# MOD-COIL-LN2-21.net
KiCad netlist of a schematic drawn in Altium Designer
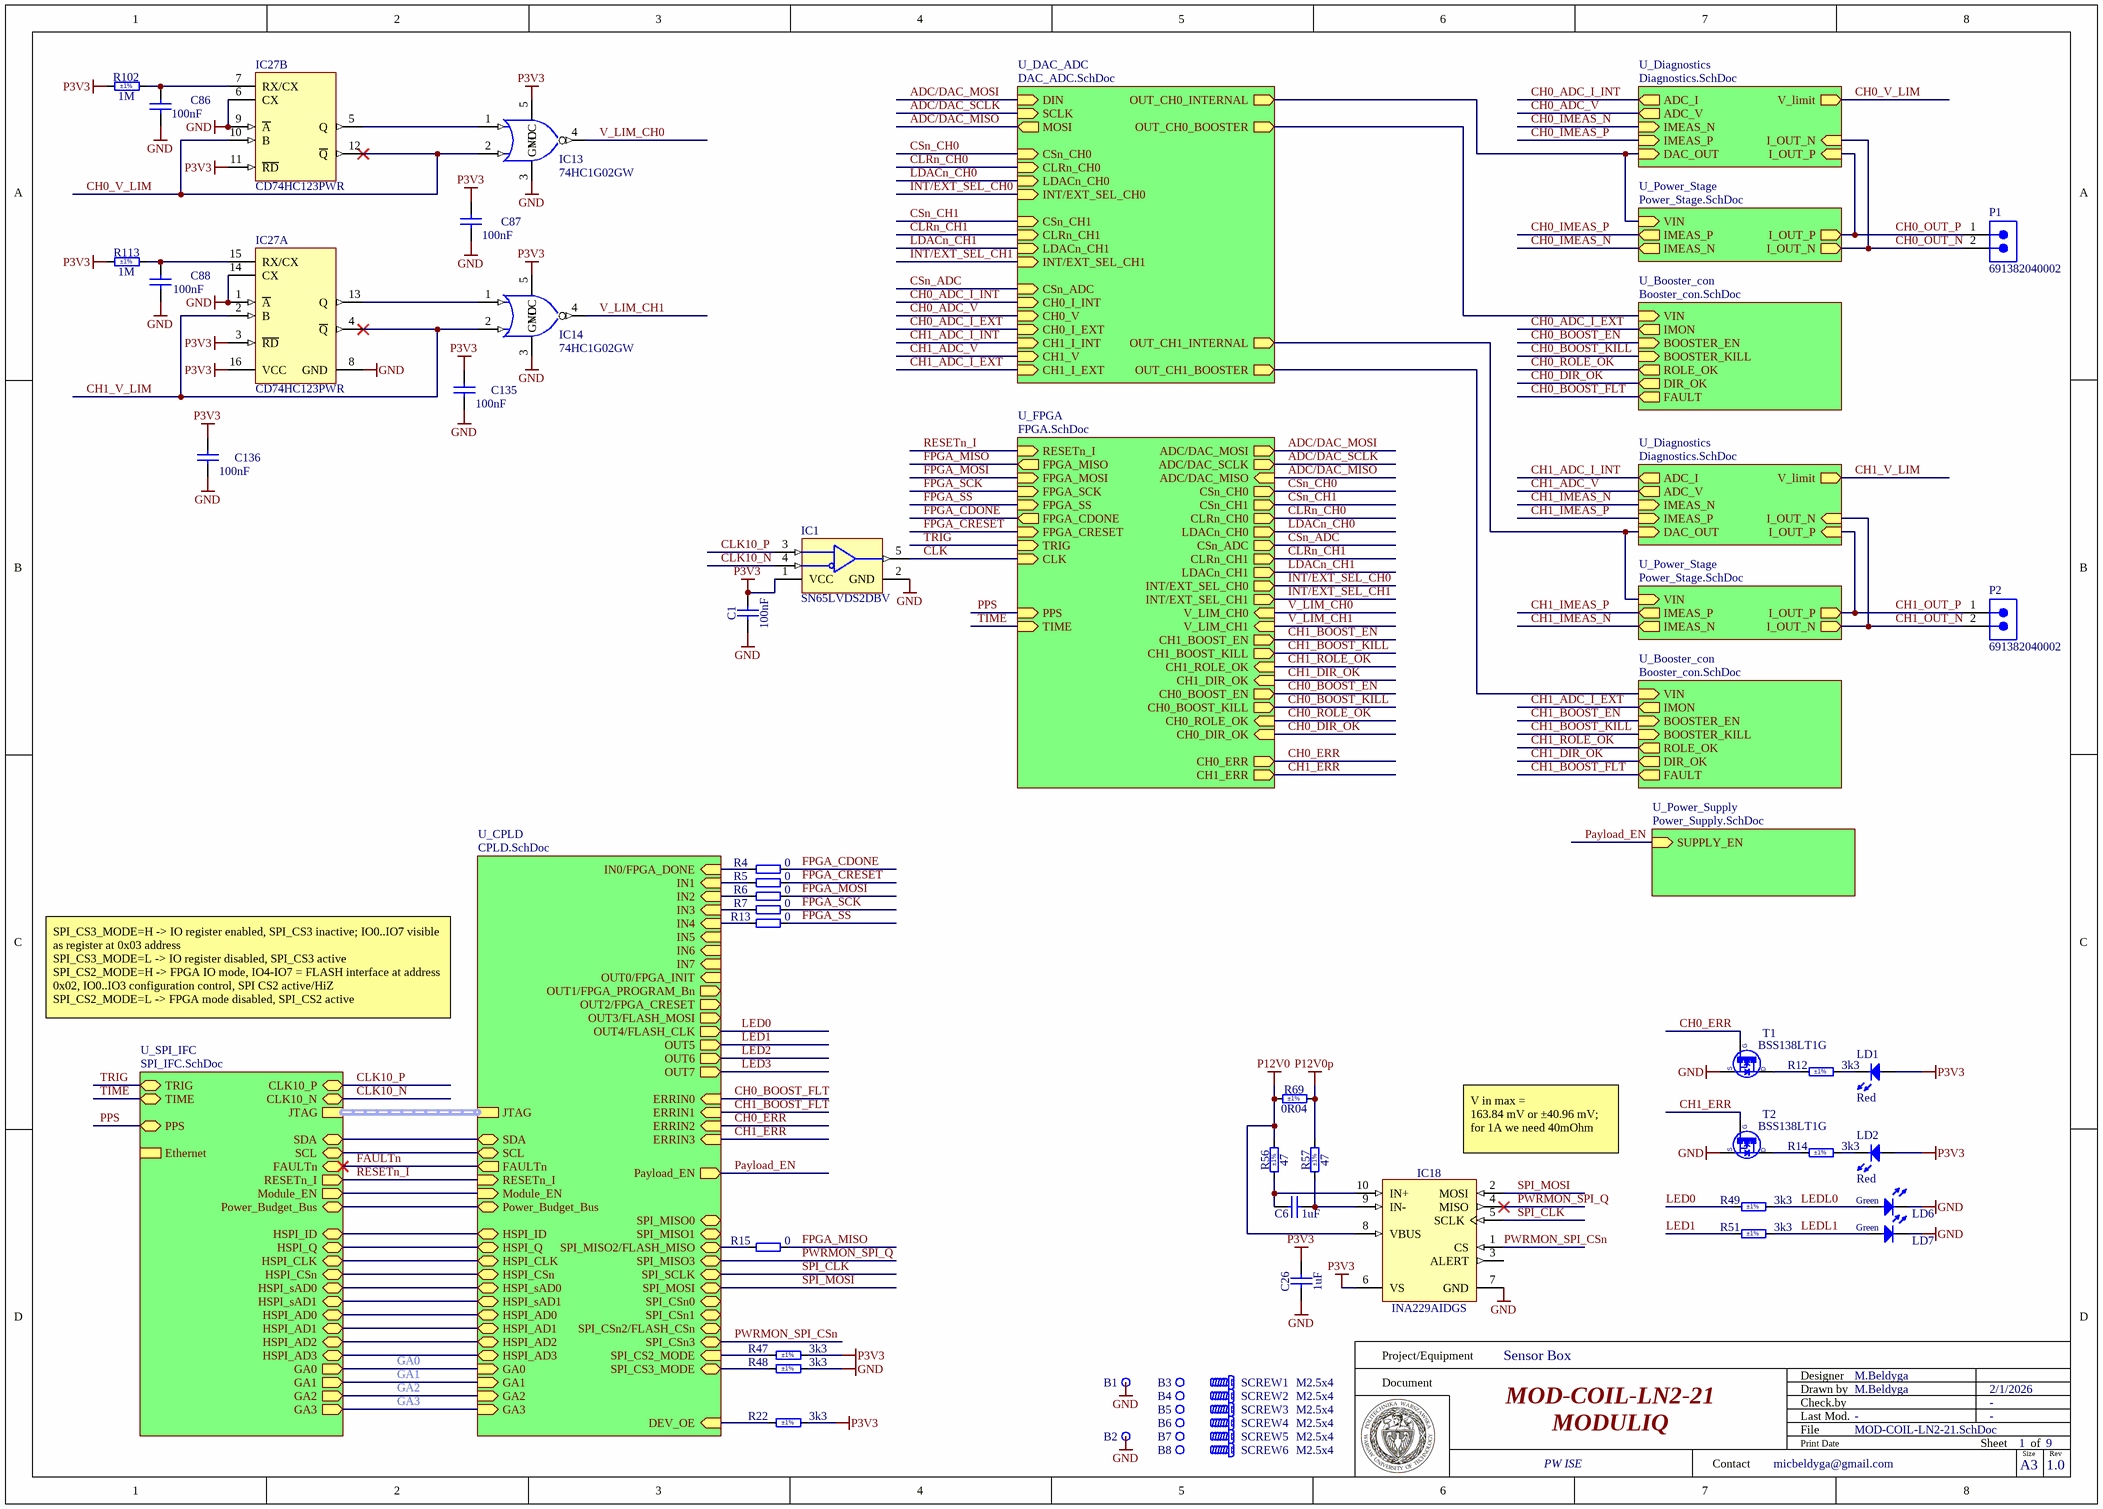
[diagram p0: MOD-COIL-LN2-21.SchDoc]

(export (version "E")
  (design (tool "Eeschema 10.0.6"))
  (components
    (comp (ref "B1")
      (value "Plated Hole")
      (footprint "MTG270_500")
      (description "Single Terminal Socket")
      (fields (field (name "PART NUMBER") "PLATED_HOLE2.7_PAD5.0") (field (name "AUTHOR") "CERN DEM JMW"))
      (libsource (lib "Eletro-mechanical") (part "Single Terminal Socket"))
    )
    (comp (ref "B2")
      (value "Plated Hole")
      (footprint "MTG270_500")
      (description "Single Terminal Socket")
      (fields (field (name "PART NUMBER") "PLATED_HOLE2.7_PAD5.0") (field (name "AUTHOR") "CERN DEM JMW"))
      (libsource (lib "Eletro-mechanical") (part "Single Terminal Socket"))
    )
    (comp (ref "B3")
      (value "Plated Hole")
      (footprint "MTG270_500")
      (description "Single Terminal Socket")
      (fields (field (name "PART NUMBER") "PLATED_HOLE2.7_PAD5.0") (field (name "AUTHOR") "CERN DEM JMW"))
      (libsource (lib "Eletro-mechanical") (part "Single Terminal Socket"))
    )
    (comp (ref "B4")
      (value "Plated Hole")
      (footprint "MTG270_500")
      (description "Single Terminal Socket")
      (fields (field (name "PART NUMBER") "PLATED_HOLE2.7_PAD5.0") (field (name "AUTHOR") "CERN DEM JMW"))
      (libsource (lib "Eletro-mechanical") (part "Single Terminal Socket"))
    )
    (comp (ref "B5")
      (value "Plated Hole")
      (footprint "MTG270_500")
      (description "Single Terminal Socket")
      (fields (field (name "PART NUMBER") "PLATED_HOLE2.7_PAD5.0") (field (name "AUTHOR") "CERN DEM JMW"))
      (libsource (lib "Eletro-mechanical") (part "Single Terminal Socket"))
    )
    (comp (ref "B6")
      (value "Plated Hole")
      (footprint "MTG270_500")
      (description "Single Terminal Socket")
      (fields (field (name "PART NUMBER") "PLATED_HOLE2.7_PAD5.0") (field (name "AUTHOR") "CERN DEM JMW"))
      (libsource (lib "Eletro-mechanical") (part "Single Terminal Socket"))
    )
    (comp (ref "B7")
      (value "Plated Hole")
      (footprint "MTG270_500")
      (description "Single Terminal Socket")
      (fields (field (name "PART NUMBER") "PLATED_HOLE2.7_PAD5.0") (field (name "AUTHOR") "CERN DEM JMW"))
      (libsource (lib "Eletro-mechanical") (part "Single Terminal Socket"))
    )
    (comp (ref "B8")
      (value "Plated Hole")
      (footprint "MTG270_500")
      (description "Single Terminal Socket")
      (fields (field (name "PART NUMBER") "PLATED_HOLE2.7_PAD5.0") (field (name "AUTHOR") "CERN DEM JMW"))
      (libsource (lib "Eletro-mechanical") (part "Single Terminal Socket"))
    )
    (comp (ref "C1")
      (value "100nF")
      (footprint "CAPC1005X55N")
      (description "Non-polarised capacitor")
      (fields
        (field (name "PART NUMBER") "CC0402_100NF_16V_10%_X7R")
        (field (name "VOLTAGE") "16V")
        (field (name "AUTHOR") "CERN DEM JLC")
      )
      (libsource (lib "Capacitors") (part "Capacitor - non polarized"))
    )
    (comp (ref "C6")
      (value "1uF")
      (footprint "CAPC1005X55N")
      (description "Non-polarised capacitor")
      (fields
        (field (name "PART NUMBER") "CC0402_1UF_16V_10%_X5R")
        (field (name "VOLTAGE") "16V")
        (field (name "AUTHOR") "CERN DEM JLC")
      )
      (libsource (lib "Capacitors") (part "Capacitor - non polarized"))
    )
    (comp (ref "C26")
      (value "1uF")
      (footprint "CAPC1005X55N")
      (description "Non-polarised capacitor")
      (fields
        (field (name "PART NUMBER") "CC0402_1UF_16V_10%_X5R")
        (field (name "VOLTAGE") "16V")
        (field (name "AUTHOR") "CERN DEM JLC")
      )
      (libsource (lib "Capacitors") (part "Capacitor - non polarized"))
    )
    (comp (ref "C86")
      (value "100nF")
      (footprint "CAPC1005X55N")
      (description "Non-polarised capacitor")
      (fields
        (field (name "PART NUMBER") "CC0402_100NF_16V_10%_X5R")
        (field (name "VOLTAGE") "16V")
        (field (name "AUTHOR") "CERN DEM JLC")
      )
      (libsource (lib "Capacitors") (part "Capacitor - non polarized"))
    )
    (comp (ref "C87")
      (value "100nF")
      (footprint "CAPC1005X55N")
      (description "Non-polarised capacitor")
      (fields
        (field (name "PART NUMBER") "CC0402_100NF_16V_10%_X5R")
        (field (name "VOLTAGE") "16V")
        (field (name "AUTHOR") "CERN DEM JLC")
      )
      (libsource (lib "Capacitors") (part "Capacitor - non polarized"))
    )
    (comp (ref "C88")
      (value "100nF")
      (footprint "CAPC1005X55N")
      (description "Non-polarised capacitor")
      (fields
        (field (name "PART NUMBER") "CC0402_100NF_16V_10%_X5R")
        (field (name "VOLTAGE") "16V")
        (field (name "AUTHOR") "CERN DEM JLC")
      )
      (libsource (lib "Capacitors") (part "Capacitor - non polarized"))
    )
    (comp (ref "C135")
      (value "100nF")
      (footprint "CAPC1005X55N")
      (description "Non-polarised capacitor")
      (fields
        (field (name "PART NUMBER") "CC0402_100NF_16V_10%_X5R")
        (field (name "VOLTAGE") "16V")
        (field (name "AUTHOR") "CERN DEM JLC")
      )
      (libsource (lib "Capacitors") (part "Capacitor - non polarized"))
    )
    (comp (ref "C136")
      (value "100nF")
      (footprint "CAPC1005X55N")
      (description "Non-polarised capacitor")
      (fields
        (field (name "PART NUMBER") "CC0402_100NF_16V_10%_X5R")
        (field (name "VOLTAGE") "16V")
        (field (name "AUTHOR") "CERN DEM JLC")
      )
      (libsource (lib "Capacitors") (part "Capacitor - non polarized"))
    )
    (comp (ref "IC1")
      (value "SN65LVDS2DBV")
      (footprint "SOT95P280X145-5N")
      (description "High-Speed Differential Line Receiver")
      (fields
        (field (name "PART NUMBER") "SN65LVDS2DBVR")
        (field (name "MANUFACTURER") "TEXAS INSTRUMENTS")
        (field (name "AUTHOR") "CERN DEM JLC")
      )
      (libsource (lib "ICs And Semiconductors") (part "SN65LVDS2DBV"))
    )
    (comp (ref "IC13")
      (value "74HC1G02GW")
      (footprint "SOT65P212X110-5N")
      (description "Single 2-Input NOR Gate")
      (fields (field (name "MANUFACTURER") "NEXPERIA") (field (name "AUTHOR") "CERN DEM MR"))
      (libsource (lib "ICs And Semiconductors") (part "741G02"))
    )
    (comp (ref "IC14")
      (value "74HC1G02GW")
      (footprint "SOT65P212X110-5N")
      (description "Single 2-Input NOR Gate")
      (fields (field (name "MANUFACTURER") "NEXPERIA") (field (name "AUTHOR") "CERN DEM MR"))
      (libsource (lib "ICs And Semiconductors") (part "741G02"))
    )
    (comp (ref "IC18")
      (value "INA229AIDGS")
      (footprint "SOP50P490X110-10N")
      (description "20-Bit, Ultra-Precise Power/Energy/Charge Monitor With SPI Interface")
      (fields (field (name "MANUFACTURER") "TEXAS INSTRUMENTS") (field (name "AUTHOR") "CERN DEM HF"))
      (libsource (lib "ICs And Semiconductors") (part "INA229"))
    )
    (comp (ref "IC27")
      (value "CD74HC123PWR")
      (footprint "SOP65P640X110-16N")
      (description "Monostable Multivibrator Dual 16-Pin TSSOP T/R - Tape and Reel (Alt: CD74HC123PW")
      (fields (field (name "MANUFACTURER") "Texas Instruments"))
      (libsource (lib "mb") (part "CD74HC123PWR"))
    )
    (comp (ref "LD1")
      (value "Red")
      (footprint "LED_AVAGO_HSMC-C120")
      (description "LED Red 1C 2A")
      (fields
        (field (name "PART NUMBER") "LED_AVAGO_HSMC-C120")
        (field (name "MANUFACTURER") "AVAGO TECHNOLOGIES")
        (field (name "AUTHOR") "CERN DEM JMW")
      )
      (libsource (lib "ICs And Semiconductors") (part "LED Red 1C 2A"))
    )
    (comp (ref "LD2")
      (value "Red")
      (footprint "LED_AVAGO_HSMC-C120")
      (description "LED Red 1C 2A")
      (fields
        (field (name "PART NUMBER") "LED_AVAGO_HSMC-C120")
        (field (name "MANUFACTURER") "AVAGO TECHNOLOGIES")
        (field (name "AUTHOR") "CERN DEM JMW")
      )
      (libsource (lib "ICs And Semiconductors") (part "LED Red 1C 2A"))
    )
    (comp (ref "LD6")
      (value "Green")
      (footprint "LED_AVAGO_HSME-C120")
      (description "LED Green 1C 2A")
      (fields
        (field (name "PART NUMBER") "LED_AVAGO_HSME-C120")
        (field (name "MANUFACTURER") "AVAGO TECHNOLOGIES")
        (field (name "AUTHOR") "CERN DEM JMW")
      )
      (libsource (lib "ICs And Semiconductors") (part "LED Green 1C 2A"))
    )
    (comp (ref "LD7")
      (value "Green")
      (footprint "LED_AVAGO_HSME-C120")
      (description "LED Green 1C 2A")
      (fields
        (field (name "PART NUMBER") "LED_AVAGO_HSME-C120")
        (field (name "MANUFACTURER") "AVAGO TECHNOLOGIES")
        (field (name "AUTHOR") "CERN DEM JMW")
      )
      (libsource (lib "ICs And Semiconductors") (part "LED Green 1C 2A"))
    )
    (comp (ref "P1")
      (value "691382040002")
      (footprint "691382040002")
      (description "WR-TBL Series 382 Horizontal PCB Header with Flanges, THT, pitch 2.5mm, 2p")
      (fields (field (name "MANUFACTURER") "Wurth Elektronik"))
      (libsource (lib "WE - Electromechanical Components") (part "TBL - 1R - 02P - Male"))
    )
    (comp (ref "P2")
      (value "691382040002")
      (footprint "691382040002")
      (description "WR-TBL Series 382 Horizontal PCB Header with Flanges, THT, pitch 2.5mm, 2p")
      (fields (field (name "MANUFACTURER") "Wurth Elektronik"))
      (libsource (lib "WE - Electromechanical Components") (part "TBL - 1R - 02P - Male"))
    )
    (comp (ref "R4")
      (value "0")
      (footprint "RESC1005X40N")
      (description "Resistor")
      (fields
        (field (name "PART NUMBER") "R0402_0R_JUMPER")
        (field (name "MANUFACTURER") "GENERIC")
        (field (name "AUTHOR") "CERN DEM JLC")
      )
      (libsource (lib "Resistors") (part "Resistor"))
    )
    (comp (ref "R5")
      (value "0")
      (footprint "RESC1005X40N")
      (description "Resistor")
      (fields
        (field (name "PART NUMBER") "R0402_0R_JUMPER")
        (field (name "MANUFACTURER") "GENERIC")
        (field (name "AUTHOR") "CERN DEM JLC")
      )
      (libsource (lib "Resistors") (part "Resistor"))
    )
    (comp (ref "R6")
      (value "0")
      (footprint "RESC1005X40N")
      (description "Resistor")
      (fields
        (field (name "PART NUMBER") "R0402_0R_JUMPER")
        (field (name "MANUFACTURER") "GENERIC")
        (field (name "AUTHOR") "CERN DEM JLC")
      )
      (libsource (lib "Resistors") (part "Resistor"))
    )
    (comp (ref "R7")
      (value "0")
      (footprint "RESC1005X40N")
      (description "Resistor")
      (fields
        (field (name "PART NUMBER") "R0402_0R_JUMPER")
        (field (name "MANUFACTURER") "GENERIC")
        (field (name "AUTHOR") "CERN DEM JLC")
      )
      (libsource (lib "Resistors") (part "Resistor"))
    )
    (comp (ref "R12")
      (value "3k3")
      (footprint "RESC1005X40N")
      (description "Resistor - 1%")
      (fields
        (field (name "TOLERANCE") "±1%")
        (field (name "PART NUMBER") "R0402_3K3_1%_0.0625W_100PPM")
        (field (name "POWER") "0.0625W")
        (field (name "AUTHOR") "CERN DEM JLC")
      )
      (libsource (lib "Resistors") (part "Resistor - 1%"))
    )
    (comp (ref "R13")
      (value "0")
      (footprint "RESC1005X40N")
      (description "Resistor")
      (fields
        (field (name "PART NUMBER") "R0402_0R_JUMPER")
        (field (name "MANUFACTURER") "GENERIC")
        (field (name "AUTHOR") "CERN DEM JLC")
      )
      (libsource (lib "Resistors") (part "Resistor"))
    )
    (comp (ref "R14")
      (value "3k3")
      (footprint "RESC1005X40N")
      (description "Resistor - 1%")
      (fields
        (field (name "TOLERANCE") "±1%")
        (field (name "PART NUMBER") "R0402_3K3_1%_0.0625W_100PPM")
        (field (name "POWER") "0.0625W")
        (field (name "AUTHOR") "CERN DEM JLC")
      )
      (libsource (lib "Resistors") (part "Resistor - 1%"))
    )
    (comp (ref "R15")
      (value "0")
      (footprint "RESC1005X40N")
      (description "Resistor")
      (fields
        (field (name "PART NUMBER") "R0402_0R_JUMPER")
        (field (name "MANUFACTURER") "GENERIC")
        (field (name "AUTHOR") "CERN DEM JLC")
      )
      (libsource (lib "Resistors") (part "Resistor"))
    )
    (comp (ref "R22")
      (value "3k3")
      (footprint "RESC1005X40N")
      (description "Resistor - 1%")
      (fields
        (field (name "TOLERANCE") "±1%")
        (field (name "PART NUMBER") "R0402_3K3_1%_0.0625W_100PPM")
        (field (name "POWER") "0.0625W")
        (field (name "AUTHOR") "CERN DEM JLC")
      )
      (libsource (lib "Resistors") (part "Resistor - 1%"))
    )
    (comp (ref "R47")
      (value "3k3")
      (footprint "RESC1005X40N")
      (description "Resistor - 1%")
      (fields
        (field (name "TOLERANCE") "±1%")
        (field (name "PART NUMBER") "R0402_3K3_1%_0.0625W_100PPM")
        (field (name "POWER") "0.0625W")
        (field (name "AUTHOR") "CERN DEM JLC")
      )
      (libsource (lib "Resistors") (part "Resistor - 1%"))
    )
    (comp (ref "R48")
      (value "3k3")
      (footprint "RESC1005X40N")
      (description "Resistor - 1%")
      (fields
        (field (name "TOLERANCE") "±1%")
        (field (name "PART NUMBER") "R0402_3K3_1%_0.0625W_100PPM")
        (field (name "POWER") "0.0625W")
        (field (name "AUTHOR") "CERN DEM JLC")
      )
      (libsource (lib "Resistors") (part "Resistor - 1%"))
    )
    (comp (ref "R49")
      (value "3k3")
      (footprint "RESC1005X40N")
      (description "Resistor - 1%")
      (fields
        (field (name "TOLERANCE") "±1%")
        (field (name "PART NUMBER") "R0402_3K3_1%_0.0625W_100PPM")
        (field (name "POWER") "0.0625W")
        (field (name "AUTHOR") "CERN DEM JLC")
      )
      (libsource (lib "Resistors") (part "Resistor - 1%"))
    )
    (comp (ref "R51")
      (value "3k3")
      (footprint "RESC1005X40N")
      (description "Resistor - 1%")
      (fields
        (field (name "TOLERANCE") "±1%")
        (field (name "PART NUMBER") "R0402_3K3_1%_0.0625W_100PPM")
        (field (name "POWER") "0.0625W")
        (field (name "AUTHOR") "CERN DEM JLC")
      )
      (libsource (lib "Resistors") (part "Resistor - 1%"))
    )
    (comp (ref "R56")
      (value "47")
      (footprint "RESC1608X55N")
      (description "Resistor - 1%")
      (fields
        (field (name "TOLERANCE") "±1%")
        (field (name "PART NUMBER") "R0603_47R_1%_0.1W_100PPM")
        (field (name "POWER") "0.1W")
        (field (name "AUTHOR") "CERN DEM JLC")
      )
      (libsource (lib "Resistors") (part "Resistor - 1%"))
    )
    (comp (ref "R57")
      (value "47")
      (footprint "RESC1608X55N")
      (description "Resistor - 1%")
      (fields
        (field (name "TOLERANCE") "±1%")
        (field (name "PART NUMBER") "R0603_47R_1%_0.1W_100PPM")
        (field (name "POWER") "0.1W")
        (field (name "AUTHOR") "CERN DEM JLC")
      )
      (libsource (lib "Resistors") (part "Resistor - 1%"))
    )
    (comp (ref "R69")
      (value "0R04")
      (footprint "RESC3216X89N")
      (description "Resistor - 1%")
      (fields
        (field (name "TOLERANCE") "±1%")
        (field (name "PART NUMBER") "R1206_0R04_1%_0.25W_75PPM_VISHAY_WSL")
        (field (name "POWER") "0.25W")
        (field (name "AUTHOR") "CERN DEM JMW")
      )
      (libsource (lib "Resistors") (part "Resistor - 1%"))
    )
    (comp (ref "R102")
      (value "1M")
      (footprint "RESC1005X40N")
      (description "Resistor - 1%")
      (fields
        (field (name "TOLERANCE") "±1%")
        (field (name "PART NUMBER") "R0402_1M_1%_0.0625W_100PPM")
        (field (name "POWER") "0.0625W")
        (field (name "AUTHOR") "CERN DEM JLC")
      )
      (libsource (lib "Resistors") (part "Resistor - 1%"))
    )
    (comp (ref "R113")
      (value "1M")
      (footprint "RESC1005X40N")
      (description "Resistor - 1%")
      (fields
        (field (name "TOLERANCE") "±1%")
        (field (name "PART NUMBER") "R0402_1M_1%_0.0625W_100PPM")
        (field (name "POWER") "0.0625W")
        (field (name "AUTHOR") "CERN DEM JLC")
      )
      (libsource (lib "Resistors") (part "Resistor - 1%"))
    )
    (comp (ref "SCREW1")
      (value "M2.5x4")
      (footprint "BOSSARD_BN5687-3061587_v")
      (description "Screw")
      (fields
        (field (name "PART NUMBER") "BOSSARD_BN5687-3061587_v")
        (field (name "MANUFACTURER") "BOSSARD")
        (field (name "AUTHOR") "CERN DEM JLC")
      )
      (libsource (lib "Eletro-mechanical") (part "Screw"))
    )
    (comp (ref "SCREW2")
      (value "M2.5x4")
      (footprint "BOSSARD_BN5687-3061587_v")
      (description "Screw")
      (fields
        (field (name "PART NUMBER") "BOSSARD_BN5687-3061587_v")
        (field (name "MANUFACTURER") "BOSSARD")
        (field (name "AUTHOR") "CERN DEM JLC")
      )
      (libsource (lib "Eletro-mechanical") (part "Screw"))
    )
    (comp (ref "SCREW3")
      (value "M2.5x4")
      (footprint "BOSSARD_BN5687-3061587_v")
      (description "Screw")
      (fields
        (field (name "PART NUMBER") "BOSSARD_BN5687-3061587_v")
        (field (name "MANUFACTURER") "BOSSARD")
        (field (name "AUTHOR") "CERN DEM JLC")
      )
      (libsource (lib "Eletro-mechanical") (part "Screw"))
    )
    (comp (ref "SCREW4")
      (value "M2.5x4")
      (footprint "BOSSARD_BN5687-3061587_v")
      (description "Screw")
      (fields
        (field (name "PART NUMBER") "BOSSARD_BN5687-3061587_v")
        (field (name "MANUFACTURER") "BOSSARD")
        (field (name "AUTHOR") "CERN DEM JLC")
      )
      (libsource (lib "Eletro-mechanical") (part "Screw"))
    )
    (comp (ref "SCREW5")
      (value "M2.5x4")
      (footprint "BOSSARD_BN5687-3061587_v")
      (description "Screw")
      (fields
        (field (name "PART NUMBER") "BOSSARD_BN5687-3061587_v")
        (field (name "MANUFACTURER") "BOSSARD")
        (field (name "AUTHOR") "CERN DEM JLC")
      )
      (libsource (lib "Eletro-mechanical") (part "Screw"))
    )
    (comp (ref "SCREW6")
      (value "M2.5x4")
      (footprint "BOSSARD_BN5687-3061587_v")
      (description "Screw")
      (fields
        (field (name "PART NUMBER") "BOSSARD_BN5687-3061587_v")
        (field (name "MANUFACTURER") "BOSSARD")
        (field (name "AUTHOR") "CERN DEM JLC")
      )
      (libsource (lib "Eletro-mechanical") (part "Screw"))
    )
    (comp (ref "T1")
      (value "BSS138LT1G")
      (footprint "SOT95P240X110-3N")
      (description "N-CHANNEL MOSFET WITH DIODE")
      (fields (field (name "AUTHOR") "CERN DEM JLC"))
      (libsource (lib "ICs And Semiconductors") (part "N-MOSFET-D 1G 2S 3D"))
    )
    (comp (ref "T2")
      (value "BSS138LT1G")
      (footprint "SOT95P240X110-3N")
      (description "N-CHANNEL MOSFET WITH DIODE")
      (fields (field (name "AUTHOR") "CERN DEM JLC"))
      (libsource (lib "ICs And Semiconductors") (part "N-MOSFET-D 1G 2S 3D"))
    )
  )
  (nets
    (net (code "11") (name "/CH0_ERR") (class "Default")
      (node (ref "T1") (pin "1") (pinfunction "G_1") (pintype "passive"))
    )
    (net (code "14") (name "/CH0_OUT_N") (class "Default")
      (node (ref "P1") (pin "2") (pinfunction "2_2") (pintype "passive"))
    )
    (net (code "15") (name "/CH0_OUT_P") (class "Default")
      (node (ref "P1") (pin "1") (pinfunction "1_1") (pintype "passive"))
    )
    (net (code "17") (name "/CH0_V_LIM") (class "Default")
      (node (ref "IC13") (pin "2") (pinfunction "A_2") (pintype "input"))
      (node (ref "IC27") (pin "10") (pinfunction "B_10") (pintype "input"))
      (node (ref "IC27") (pin "12") (pinfunction "~{Q}_12") (pintype "output"))
    )
    (net (code "25") (name "/CH1_ERR") (class "Default")
      (node (ref "T2") (pin "1") (pinfunction "G_1") (pintype "passive"))
    )
    (net (code "28") (name "/CH1_OUT_N") (class "Default")
      (node (ref "P2") (pin "2") (pinfunction "2_2") (pintype "passive"))
    )
    (net (code "29") (name "/CH1_OUT_P") (class "Default")
      (node (ref "P2") (pin "1") (pinfunction "1_1") (pintype "passive"))
    )
    (net (code "31") (name "/CH1_V_LIM") (class "Default")
      (node (ref "IC14") (pin "2") (pinfunction "A_2") (pintype "input"))
      (node (ref "IC27") (pin "2") (pinfunction "B_2") (pintype "input"))
      (node (ref "IC27") (pin "4") (pinfunction "~{Q}_4") (pintype "output"))
    )
    (net (code "32") (name "/CLK") (class "Default")
      (node (ref "IC1") (pin "5") (pinfunction "R_5") (pintype "output"))
    )
    (net (code "33") (name "/CLK10_N") (class "Default")
      (node (ref "IC1") (pin "4") (pinfunction "B_4") (pintype "input"))
    )
    (net (code "34") (name "/CLK10_P") (class "Default")
      (node (ref "IC1") (pin "3") (pinfunction "A_3") (pintype "input"))
    )
    (net (code "40") (name "/DEV_OE") (class "Default")
      (node (ref "R22") (pin "1") (pinfunction "1_1") (pintype "passive"))
    )
    (net (code "43") (name "/FPGA_CDONE") (class "Default")
      (node (ref "R4") (pin "2") (pinfunction "2_2") (pintype "passive"))
    )
    (net (code "44") (name "/FPGA_CRESET") (class "Default")
      (node (ref "R5") (pin "2") (pinfunction "2_2") (pintype "passive"))
    )
    (net (code "45") (name "/FPGA_MISO") (class "Default")
      (node (ref "R15") (pin "2") (pinfunction "2_2") (pintype "passive"))
    )
    (net (code "46") (name "/FPGA_MOSI") (class "Default")
      (node (ref "R6") (pin "2") (pinfunction "2_2") (pintype "passive"))
    )
    (net (code "47") (name "/FPGA_SCK") (class "Default")
      (node (ref "R7") (pin "2") (pinfunction "2_2") (pintype "passive"))
    )
    (net (code "48") (name "/FPGA_SS") (class "Default")
      (node (ref "R13") (pin "2") (pinfunction "2_2") (pintype "passive"))
    )
    (net (code "63") (name "/IN0{slash}FPGA_DONE") (class "Default")
      (node (ref "R4") (pin "1") (pinfunction "1_1") (pintype "passive"))
    )
    (net (code "64") (name "/IN1") (class "Default")
      (node (ref "R5") (pin "1") (pinfunction "1_1") (pintype "passive"))
    )
    (net (code "65") (name "/IN2") (class "Default")
      (node (ref "R6") (pin "1") (pinfunction "1_1") (pintype "passive"))
    )
    (net (code "66") (name "/IN3") (class "Default")
      (node (ref "R7") (pin "1") (pinfunction "1_1") (pintype "passive"))
    )
    (net (code "67") (name "/IN4") (class "Default")
      (node (ref "R13") (pin "1") (pinfunction "1_1") (pintype "passive"))
    )
    (net (code "76") (name "/LED0") (class "Default")
      (node (ref "R49") (pin "1") (pinfunction "1_1") (pintype "passive"))
    )
    (net (code "77") (name "/LED1") (class "Default")
      (node (ref "R51") (pin "1") (pinfunction "1_1") (pintype "passive"))
    )
    (net (code "80") (name "/LEDL0") (class "Default")
      (node (ref "LD6") (pin "2") (pinfunction "A_2") (pintype "passive"))
      (node (ref "R49") (pin "2") (pinfunction "2_2") (pintype "passive"))
    )
    (net (code "81") (name "/LEDL1") (class "Default")
      (node (ref "LD7") (pin "2") (pinfunction "A_2") (pintype "passive"))
      (node (ref "R51") (pin "2") (pinfunction "2_2") (pintype "passive"))
    )
    (net (code "92") (name "/PWRMON_SPI_CSn") (class "Default")
      (node (ref "IC18") (pin "1") (pinfunction "CS_1") (pintype "input"))
    )
    (net (code "93") (name "/PWRMON_SPI_Q") (class "Default")
      (node (ref "IC18") (pin "4") (pinfunction "MISO_4") (pintype "output+no_connect"))
    )
    (net (code "99") (name "/SPI_CLK") (class "Default")
      (node (ref "IC18") (pin "5") (pinfunction "SCLK_5") (pintype "input"))
    )
    (net (code "100") (name "/SPI_CS2_MODE") (class "Default")
      (node (ref "R47") (pin "1") (pinfunction "1_1") (pintype "passive"))
    )
    (net (code "101") (name "/SPI_CS3_MODE") (class "Default")
      (node (ref "R48") (pin "1") (pinfunction "1_1") (pintype "passive"))
    )
    (net (code "107") (name "/SPI_MISO2{slash}FLASH_MISO") (class "Default")
      (node (ref "R15") (pin "1") (pinfunction "1_1") (pintype "passive"))
    )
    (net (code "108") (name "/SPI_MOSI") (class "Default")
      (node (ref "IC18") (pin "2") (pinfunction "MOSI_2") (pintype "input"))
    )
    (net (code "111") (name "/V_LIM_CH0") (class "Default")
      (node (ref "IC13") (pin "4") (pinfunction "Y_4") (pintype "output"))
    )
    (net (code "112") (name "/V_LIM_CH1") (class "Default")
      (node (ref "IC14") (pin "4") (pinfunction "Y_4") (pintype "output"))
    )
    (net (code "113") (name "GND") (class "Default")
      (node (ref "B1") (pin "1") (pinfunction "1_1") (pintype "bidirectional"))
      (node (ref "B2") (pin "1") (pinfunction "1_1") (pintype "bidirectional"))
      (node (ref "C1") (pin "1") (pinfunction "1_1") (pintype "passive"))
      (node (ref "C135") (pin "1") (pinfunction "1_1") (pintype "passive"))
      (node (ref "C136") (pin "1") (pinfunction "1_1") (pintype "passive"))
      (node (ref "C26") (pin "1") (pinfunction "1_1") (pintype "passive"))
      (node (ref "C86") (pin "1") (pinfunction "1_1") (pintype "passive"))
      (node (ref "C87") (pin "1") (pinfunction "1_1") (pintype "passive"))
      (node (ref "C88") (pin "1") (pinfunction "1_1") (pintype "passive"))
      (node (ref "IC1") (pin "2") (pinfunction "GND_2") (pintype "power_in"))
      (node (ref "IC13") (pin "3") (pinfunction "GND_3") (pintype "power_in"))
      (node (ref "IC14") (pin "3") (pinfunction "GND_3") (pintype "power_in"))
      (node (ref "IC18") (pin "7") (pinfunction "GND_7") (pintype "power_in"))
      (node (ref "IC27") (pin "1") (pinfunction "~{A}_1") (pintype "input"))
      (node (ref "IC27") (pin "14") (pinfunction "CX_14") (pintype "passive"))
      (node (ref "IC27") (pin "6") (pinfunction "CX_6") (pintype "passive"))
      (node (ref "IC27") (pin "8") (pinfunction "GND_8") (pintype "power_in"))
      (node (ref "IC27") (pin "9") (pinfunction "~{A}_9") (pintype "input"))
      (node (ref "LD6") (pin "1") (pinfunction "C_1") (pintype "passive"))
      (node (ref "LD7") (pin "1") (pinfunction "C_1") (pintype "passive"))
      (node (ref "R48") (pin "2") (pinfunction "2_2") (pintype "passive"))
      (node (ref "T1") (pin "2") (pinfunction "S_2") (pintype "passive"))
      (node (ref "T2") (pin "2") (pinfunction "S_2") (pintype "passive"))
    )
    (net (code "114") (name "Net-(IC13-B)") (class "Default")
      (node (ref "IC13") (pin "1") (pinfunction "B_1") (pintype "input"))
      (node (ref "IC27") (pin "5") (pinfunction "Q_5") (pintype "output"))
    )
    (net (code "115") (name "Net-(IC14-B)") (class "Default")
      (node (ref "IC14") (pin "1") (pinfunction "B_1") (pintype "input"))
      (node (ref "IC27") (pin "13") (pinfunction "Q_13") (pintype "output"))
    )
    (net (code "116") (name "Net-(IC18-IN+)") (class "Default")
      (node (ref "C6") (pin "2") (pinfunction "2_2") (pintype "passive"))
      (node (ref "IC18") (pin "10") (pinfunction "IN+_10") (pintype "input"))
      (node (ref "R56") (pin "1") (pinfunction "1_1") (pintype "passive"))
    )
    (net (code "117") (name "Net-(IC18-IN-)") (class "Default")
      (node (ref "C6") (pin "1") (pinfunction "1_1") (pintype "passive"))
      (node (ref "IC18") (pin "9") (pinfunction "IN-_9") (pintype "input"))
      (node (ref "R57") (pin "1") (pinfunction "1_1") (pintype "passive"))
    )
    (net (code "118") (name "Net-(IC27A-RX{slash}CX)") (class "Default")
      (node (ref "C88") (pin "2") (pinfunction "2_2") (pintype "passive"))
      (node (ref "IC27") (pin "15") (pinfunction "RX/CX_15") (pintype "passive"))
      (node (ref "R113") (pin "2") (pinfunction "2_2") (pintype "passive"))
    )
    (net (code "119") (name "Net-(IC27B-RX{slash}CX)") (class "Default")
      (node (ref "C86") (pin "2") (pinfunction "2_2") (pintype "passive"))
      (node (ref "IC27") (pin "7") (pinfunction "RX/CX_7") (pintype "passive"))
      (node (ref "R102") (pin "2") (pinfunction "2_2") (pintype "passive"))
    )
    (net (code "120") (name "Net-(LD1-C)") (class "Default")
      (node (ref "LD1") (pin "1") (pinfunction "C_1") (pintype "passive"))
      (node (ref "R12") (pin "2") (pinfunction "2_2") (pintype "passive"))
    )
    (net (code "121") (name "Net-(LD2-C)") (class "Default")
      (node (ref "LD2") (pin "1") (pinfunction "C_1") (pintype "passive"))
      (node (ref "R14") (pin "2") (pinfunction "2_2") (pintype "passive"))
    )
    (net (code "122") (name "Net-(T1-D)") (class "Default")
      (node (ref "R12") (pin "1") (pinfunction "1_1") (pintype "passive"))
      (node (ref "T1") (pin "3") (pinfunction "D_3") (pintype "passive"))
    )
    (net (code "123") (name "Net-(T2-D)") (class "Default")
      (node (ref "R14") (pin "1") (pinfunction "1_1") (pintype "passive"))
      (node (ref "T2") (pin "3") (pinfunction "D_3") (pintype "passive"))
    )
    (net (code "124") (name "P3V3") (class "Default")
      (node (ref "C1") (pin "2") (pinfunction "2_2") (pintype "passive"))
      (node (ref "C135") (pin "2") (pinfunction "2_2") (pintype "passive"))
      (node (ref "C136") (pin "2") (pinfunction "2_2") (pintype "passive"))
      (node (ref "C26") (pin "2") (pinfunction "2_2") (pintype "passive"))
      (node (ref "C87") (pin "2") (pinfunction "2_2") (pintype "passive"))
      (node (ref "IC1") (pin "1") (pinfunction "VCC_1") (pintype "power_in"))
      (node (ref "IC13") (pin "5") (pinfunction "VCC_5") (pintype "power_in"))
      (node (ref "IC14") (pin "5") (pinfunction "VCC_5") (pintype "power_in"))
      (node (ref "IC18") (pin "6") (pinfunction "VS_6") (pintype "power_in"))
      (node (ref "IC27") (pin "11") (pinfunction "~{RD}_11") (pintype "input"))
      (node (ref "IC27") (pin "16") (pinfunction "VCC_16") (pintype "power_in"))
      (node (ref "IC27") (pin "3") (pinfunction "~{RD}_3") (pintype "input"))
      (node (ref "LD1") (pin "2") (pinfunction "A_2") (pintype "passive"))
      (node (ref "LD2") (pin "2") (pinfunction "A_2") (pintype "passive"))
      (node (ref "R102") (pin "1") (pinfunction "1_1") (pintype "passive"))
      (node (ref "R113") (pin "1") (pinfunction "1_1") (pintype "passive"))
      (node (ref "R22") (pin "2") (pinfunction "2_2") (pintype "passive"))
      (node (ref "R47") (pin "2") (pinfunction "2_2") (pintype "passive"))
    )
    (net (code "125") (name "P12V0") (class "Default")
      (node (ref "IC18") (pin "8") (pinfunction "VBUS_8") (pintype "input"))
      (node (ref "R56") (pin "2") (pinfunction "2_2") (pintype "passive"))
      (node (ref "R69") (pin "1") (pinfunction "1_1") (pintype "passive"))
    )
    (net (code "126") (name "P12V0p") (class "Default")
      (node (ref "R57") (pin "2") (pinfunction "2_2") (pintype "passive"))
      (node (ref "R69") (pin "2") (pinfunction "2_2") (pintype "passive"))
    )
    (net (code "127") (name "unconnected-(B3-Pad1)") (class "Default")
      (node (ref "B3") (pin "1") (pinfunction "1_1") (pintype "bidirectional"))
    )
    (net (code "128") (name "unconnected-(B4-Pad1)") (class "Default")
      (node (ref "B4") (pin "1") (pinfunction "1_1") (pintype "bidirectional"))
    )
    (net (code "129") (name "unconnected-(B5-Pad1)") (class "Default")
      (node (ref "B5") (pin "1") (pinfunction "1_1") (pintype "bidirectional"))
    )
    (net (code "130") (name "unconnected-(B6-Pad1)") (class "Default")
      (node (ref "B6") (pin "1") (pinfunction "1_1") (pintype "bidirectional"))
    )
    (net (code "131") (name "unconnected-(B7-Pad1)") (class "Default")
      (node (ref "B7") (pin "1") (pinfunction "1_1") (pintype "bidirectional"))
    )
    (net (code "132") (name "unconnected-(B8-Pad1)") (class "Default")
      (node (ref "B8") (pin "1") (pinfunction "1_1") (pintype "bidirectional"))
    )
    (net (code "133") (name "unconnected-(IC18-ALERT-Pad3)") (class "Default")
      (node (ref "IC18") (pin "3") (pinfunction "ALERT_3") (pintype "output"))
    )
  )
)
